# EPS_MPPT_X_Boost-Converter.net
KiCad netlist of a schematic drawn in Altium Designer
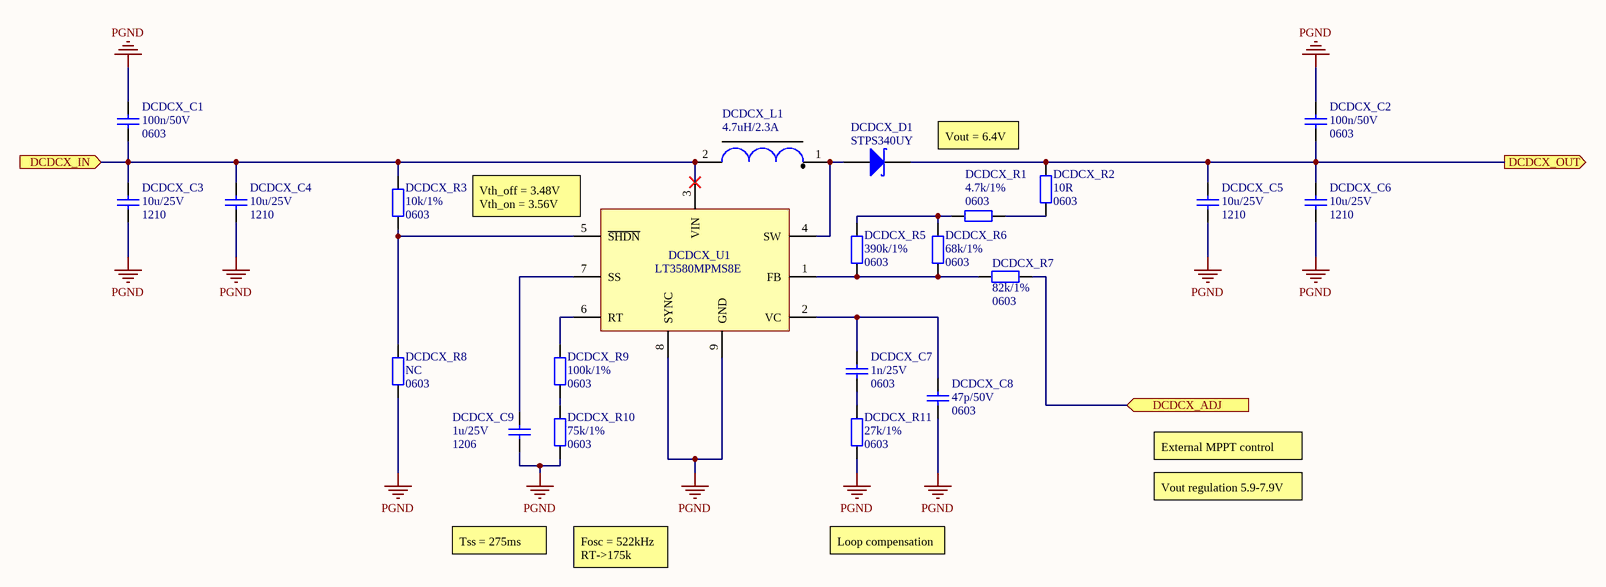
[diagram p0: EPS_MPPT_X_Boost-Converter.SchDoc]

(export (version "E")
  (design (tool "Eeschema 10.0.6"))
  (components
    (comp (ref "DCDCX_C1")
      (value "100n/50V")
      (footprint "SMD_Capacitor_0603")
      (description "Ceramic Cap Kemet COTS 100n/50V X7R 0603")
      (fields
        (field (name "MANUFACTURER") "Kemet")
        (field (name "MANUFACTURERPARTNUMBER") "C0603T104K5RALTU")
        (field (name "PACKAGE") "0603")
      )
      (libsource (lib "capacitors") (part "Cer_C0603T104K5RALTU"))
    )
    (comp (ref "DCDCX_C2")
      (value "100n/50V")
      (footprint "SMD_Capacitor_0603")
      (description "Ceramic Cap Kemet COTS 100n/50V X7R 0603")
      (fields
        (field (name "MANUFACTURER") "Kemet")
        (field (name "MANUFACTURERPARTNUMBER") "C0603T104K5RALTU")
        (field (name "PACKAGE") "0603")
      )
      (libsource (lib "capacitors") (part "Cer_C0603T104K5RALTU"))
    )
    (comp (ref "DCDCX_C3")
      (value "10u/25V")
      (footprint "SMD_Capacitor_1210")
      (description "Ceramic Cap Murata Automotive 10u/25V X7R 1210")
      (fields
        (field (name "MANUFACTURER") "Murata")
        (field (name "MANUFACTURERPARTNUMBER") "GCJ32ER71E106KA12L")
        (field (name "PACKAGE") "1210")
      )
      (libsource (lib "capacitors") (part "Cer_GCJ32ER71E106KA12L"))
    )
    (comp (ref "DCDCX_C4")
      (value "10u/25V")
      (footprint "SMD_Capacitor_1210")
      (description "Ceramic Cap Murata Automotive 10u/25V X7R 1210")
      (fields
        (field (name "MANUFACTURER") "Murata")
        (field (name "MANUFACTURERPARTNUMBER") "GCJ32ER71E106KA12L")
        (field (name "PACKAGE") "1210")
      )
      (libsource (lib "capacitors") (part "Cer_GCJ32ER71E106KA12L"))
    )
    (comp (ref "DCDCX_C5")
      (value "10u/25V")
      (footprint "SMD_Capacitor_1210")
      (description "Ceramic Cap Murata Automotive 10u/25V X7R 1210")
      (fields
        (field (name "MANUFACTURER") "Murata")
        (field (name "MANUFACTURERPARTNUMBER") "GCJ32ER71E106KA12L")
        (field (name "PACKAGE") "1210")
      )
      (libsource (lib "capacitors") (part "Cer_GCJ32ER71E106KA12L"))
    )
    (comp (ref "DCDCX_C6")
      (value "10u/25V")
      (footprint "SMD_Capacitor_1210")
      (description "Ceramic Cap Murata Automotive 10u/25V X7R 1210")
      (fields
        (field (name "MANUFACTURER") "Murata")
        (field (name "MANUFACTURERPARTNUMBER") "GCJ32ER71E106KA12L")
        (field (name "PACKAGE") "1210")
      )
      (libsource (lib "capacitors") (part "Cer_GCJ32ER71E106KA12L"))
    )
    (comp (ref "DCDCX_C7")
      (value "1n/25V")
      (footprint "SMD_Capacitor_0603")
      (description "Cap")
      (fields (field (name "PACKAGE") "0603"))
      (libsource (lib "capacitors") (part "Cap"))
    )
    (comp (ref "DCDCX_C8")
      (value "47p/50V")
      (footprint "SMD_Capacitor_0603")
      (description "Cap")
      (fields (field (name "PACKAGE") "0603"))
      (libsource (lib "capacitors") (part "Cap"))
    )
    (comp (ref "DCDCX_C9")
      (value "1u/25V")
      (footprint "SMD_Capacitor_1206")
      (description "Ceramic Cap Kemet COTS 1u/25V X7R 1206")
      (fields
        (field (name "MANUFACTURERPARTNUMBER") "C1206T105K3RALTU")
        (field (name "MANUFACTURER") "Kemet")
        (field (name "PACKAGE") "1206")
      )
      (libsource (lib "capacitors") (part "Cer_C1206T105K3RALTU"))
    )
    (comp (ref "DCDCX_D1")
      (value "STPS340UY")
      (footprint "DO-214AA")
      (description "3A/40V Power Schottky Rectifier.")
      (fields (field (name "MANUFACTURER") "STMicroelectronics"))
      (libsource (lib "diodes") (part "STPS340x"))
    )
    (comp (ref "DCDCX_L1")
      (value "4.7uH/2.3A")
      (footprint "Coilcraft_MSS6132")
      (description "Coilcraft MSS6132 Inductor, L=4.7uH, Irise20deg=2.3A, ESR=43mR, SRF=65MHz.")
      (fields
        (field (name "MANUFACTURER") "Coilcraft")
        (field (name "MANUFACTURERPARTNUMBER") "MSS6132-472MLx")
      )
      (libsource (lib "inductors") (part "MSS6132-472MLx"))
    )
    (comp (ref "DCDCX_R1")
      (value "4.7k/1%")
      (footprint "SMD_Resistor_0603")
      (fields (field (name "PACKAGE") "0603"))
      (libsource (lib "") (part "Res_2"))
    )
    (comp (ref "DCDCX_R2")
      (value "10R")
      (footprint "SMD_Resistor_0603")
      (fields (field (name "PACKAGE") "0603"))
      (libsource (lib "") (part "Res_1"))
    )
    (comp (ref "DCDCX_R3")
      (value "10k/1%")
      (footprint "SMD_Resistor_0603")
      (fields (field (name "PACKAGE") "0603"))
      (libsource (lib "resistors") (part "Res"))
    )
    (comp (ref "DCDCX_R5")
      (value "390k/1%")
      (footprint "SMD_Resistor_0603")
      (fields (field (name "PACKAGE") "0603"))
      (libsource (lib "resistors") (part "Res"))
    )
    (comp (ref "DCDCX_R6")
      (value "68k/1%")
      (footprint "SMD_Resistor_0603")
      (fields (field (name "PACKAGE") "0603"))
      (libsource (lib "resistors") (part "Res"))
    )
    (comp (ref "DCDCX_R7")
      (value "82k/1%")
      (footprint "SMD_Resistor_0603")
      (fields (field (name "PACKAGE") "0603"))
      (libsource (lib "") (part "Res_2"))
    )
    (comp (ref "DCDCX_R8")
      (value "NC")
      (footprint "SMD_Resistor_0603")
      (fields (field (name "PACKAGE") "0603"))
      (libsource (lib "resistors") (part "Res"))
    )
    (comp (ref "DCDCX_R9")
      (value "100k/1%")
      (footprint "SMD_Resistor_0603")
      (fields (field (name "PACKAGE") "0603"))
      (libsource (lib "resistors") (part "Res"))
    )
    (comp (ref "DCDCX_R10")
      (value "75k/1%")
      (footprint "SMD_Resistor_0603")
      (fields (field (name "PACKAGE") "0603"))
      (libsource (lib "resistors") (part "Res"))
    )
    (comp (ref "DCDCX_R11")
      (value "27k/1%")
      (footprint "SMD_Resistor_0603")
      (fields (field (name "PACKAGE") "0603"))
      (libsource (lib "resistors") (part "Res"))
    )
    (comp (ref "DCDCX_U1")
      (value "~")
      (footprint "LT-MS8E-8-1880X1680TP_N")
      (description "Boost Conv 2A, Soft-Start, Synchro")
      (fields
        (field (name "MANUFACTURER") "Linear Technology")
        (field (name "MANUFACTURERPARTNUMBER") "LT3580MPMS8E")
      )
      (libsource (lib "microcircuits") (part "LT3580MPMS8E"))
    )
  )
  (nets
    (net (code "1") (name "/DCDCX_ADJ") (class "Default")
      (node (ref "DCDCX_R7") (pin "2") (pinfunction "2_2") (pintype "passive"))
    )
    (net (code "2") (name "/DCDCX_IN") (class "Default")
      (node (ref "DCDCX_C1") (pin "2") (pinfunction "2_2") (pintype "passive"))
      (node (ref "DCDCX_C3") (pin "1") (pinfunction "1_1") (pintype "passive"))
      (node (ref "DCDCX_C4") (pin "1") (pinfunction "1_1") (pintype "passive"))
      (node (ref "DCDCX_L1") (pin "2") (pinfunction "2_2") (pintype "passive"))
      (node (ref "DCDCX_R3") (pin "1") (pinfunction "1_1") (pintype "passive"))
      (node (ref "DCDCX_U1") (pin "3") (pinfunction "VIN_3") (pintype "power_in"))
    )
    (net (code "3") (name "/DCDCX_OUT") (class "Default")
      (node (ref "DCDCX_C2") (pin "2") (pinfunction "2_2") (pintype "passive"))
      (node (ref "DCDCX_C5") (pin "1") (pinfunction "1_1") (pintype "passive"))
      (node (ref "DCDCX_C6") (pin "1") (pinfunction "1_1") (pintype "passive"))
      (node (ref "DCDCX_D1") (pin "K") (pinfunction "K_K") (pintype "passive"))
      (node (ref "DCDCX_R2") (pin "2") (pinfunction "2_2") (pintype "passive"))
    )
    (net (code "4") (name "Net-(DCDCX_C7-Pad2)") (class "Default")
      (node (ref "DCDCX_C7") (pin "2") (pinfunction "2_2") (pintype "passive"))
      (node (ref "DCDCX_R11") (pin "1") (pinfunction "1_1") (pintype "passive"))
    )
    (net (code "5") (name "Net-(DCDCX_R1-Pad1)") (class "Default")
      (node (ref "DCDCX_R1") (pin "1") (pinfunction "1_1") (pintype "passive"))
      (node (ref "DCDCX_R5") (pin "1") (pinfunction "1_1") (pintype "passive"))
      (node (ref "DCDCX_R6") (pin "1") (pinfunction "1_1") (pintype "passive"))
    )
    (net (code "6") (name "Net-(DCDCX_R1-Pad2)") (class "Default")
      (node (ref "DCDCX_R1") (pin "2") (pinfunction "2_2") (pintype "passive"))
      (node (ref "DCDCX_R2") (pin "1") (pinfunction "1_1") (pintype "passive"))
    )
    (net (code "7") (name "Net-(DCDCX_R10-Pad1)") (class "Default")
      (node (ref "DCDCX_R10") (pin "1") (pinfunction "1_1") (pintype "passive"))
      (node (ref "DCDCX_R9") (pin "2") (pinfunction "2_2") (pintype "passive"))
    )
    (net (code "8") (name "Net-(DCDCX_U1-FB)") (class "Default")
      (node (ref "DCDCX_R5") (pin "2") (pinfunction "2_2") (pintype "passive"))
      (node (ref "DCDCX_R6") (pin "2") (pinfunction "2_2") (pintype "passive"))
      (node (ref "DCDCX_R7") (pin "1") (pinfunction "1_1") (pintype "passive"))
      (node (ref "DCDCX_U1") (pin "1") (pinfunction "FB_1") (pintype "passive"))
    )
    (net (code "9") (name "Net-(DCDCX_U1-RT)") (class "Default")
      (node (ref "DCDCX_R9") (pin "1") (pinfunction "1_1") (pintype "passive"))
      (node (ref "DCDCX_U1") (pin "6") (pinfunction "RT_6") (pintype "passive"))
    )
    (net (code "10") (name "Net-(DCDCX_U1-SS)") (class "Default")
      (node (ref "DCDCX_C9") (pin "1") (pinfunction "1_1") (pintype "passive"))
      (node (ref "DCDCX_U1") (pin "7") (pinfunction "SS_7") (pintype "passive"))
    )
    (net (code "11") (name "Net-(DCDCX_U1-SW)") (class "Default")
      (node (ref "DCDCX_D1") (pin "A") (pinfunction "A_A") (pintype "passive"))
      (node (ref "DCDCX_L1") (pin "1") (pinfunction "1_1") (pintype "passive"))
      (node (ref "DCDCX_U1") (pin "4") (pinfunction "SW_4") (pintype "passive"))
    )
    (net (code "12") (name "Net-(DCDCX_U1-VC)") (class "Default")
      (node (ref "DCDCX_C7") (pin "1") (pinfunction "1_1") (pintype "passive"))
      (node (ref "DCDCX_C8") (pin "1") (pinfunction "1_1") (pintype "passive"))
      (node (ref "DCDCX_U1") (pin "2") (pinfunction "VC_2") (pintype "passive"))
    )
    (net (code "13") (name "Net-(DCDCX_U1-~{SHDN})") (class "Default")
      (node (ref "DCDCX_R3") (pin "2") (pinfunction "2_2") (pintype "passive"))
      (node (ref "DCDCX_R8") (pin "1") (pinfunction "1_1") (pintype "passive"))
      (node (ref "DCDCX_U1") (pin "5") (pinfunction "~{SHDN}_5") (pintype "passive"))
    )
    (net (code "14") (name "PGND") (class "Default")
      (node (ref "DCDCX_C1") (pin "1") (pinfunction "1_1") (pintype "passive"))
      (node (ref "DCDCX_C2") (pin "1") (pinfunction "1_1") (pintype "passive"))
      (node (ref "DCDCX_C3") (pin "2") (pinfunction "2_2") (pintype "passive"))
      (node (ref "DCDCX_C4") (pin "2") (pinfunction "2_2") (pintype "passive"))
      (node (ref "DCDCX_C5") (pin "2") (pinfunction "2_2") (pintype "passive"))
      (node (ref "DCDCX_C6") (pin "2") (pinfunction "2_2") (pintype "passive"))
      (node (ref "DCDCX_C8") (pin "2") (pinfunction "2_2") (pintype "passive"))
      (node (ref "DCDCX_C9") (pin "2") (pinfunction "2_2") (pintype "passive"))
      (node (ref "DCDCX_R10") (pin "2") (pinfunction "2_2") (pintype "passive"))
      (node (ref "DCDCX_R11") (pin "2") (pinfunction "2_2") (pintype "passive"))
      (node (ref "DCDCX_R8") (pin "2") (pinfunction "2_2") (pintype "passive"))
      (node (ref "DCDCX_U1") (pin "8") (pinfunction "SYNC_8") (pintype "passive"))
      (node (ref "DCDCX_U1") (pin "9") (pinfunction "GND_9") (pintype "passive"))
    )
  )
)
